# connectors.net
KiCad netlist of a schematic drawn in Altium Designer
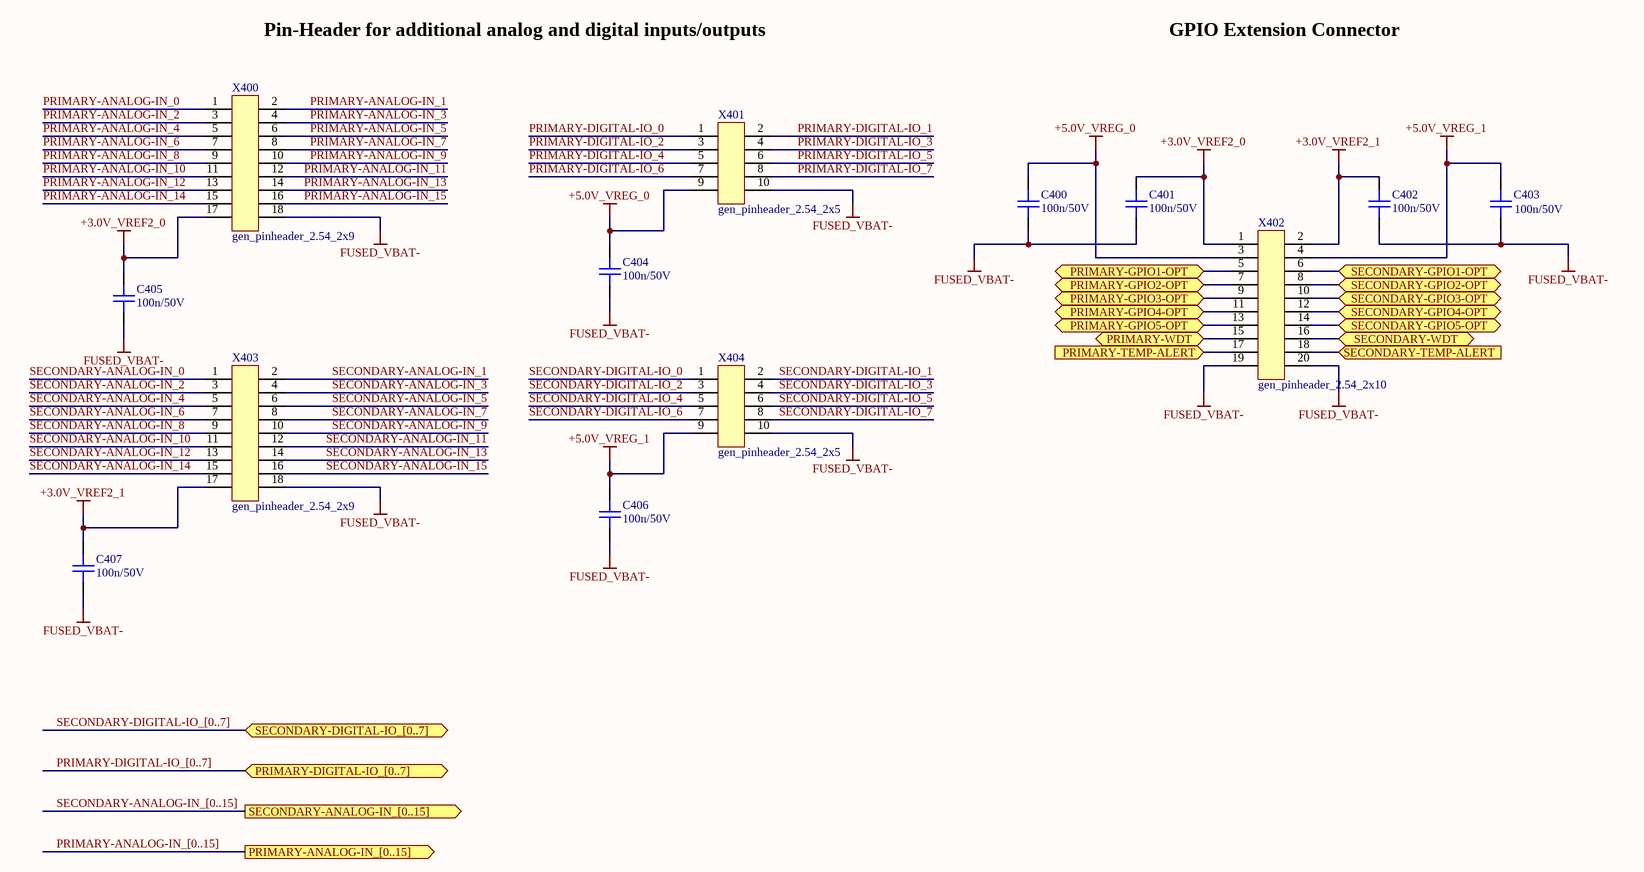
[diagram p0: connectors.SchDoc]

(export (version "E")
  (design (tool "Eeschema 10.0.6"))
  (components
    (comp (ref "C400")
      (value "100n/50V")
      (footprint "CAPC1608X08N")
      (description "MLCC")
      (fields (field (name "PART NUMBER") "gen_C_ceramic_100n_50V_X7R_0603"))
      (libsource (lib "OE750") (part "C"))
    )
    (comp (ref "C401")
      (value "100n/50V")
      (footprint "CAPC1608X08N")
      (description "MLCC")
      (fields (field (name "PART NUMBER") "gen_C_ceramic_100n_50V_X7R_0603"))
      (libsource (lib "OE750") (part "C"))
    )
    (comp (ref "C402")
      (value "100n/50V")
      (footprint "CAPC1608X08N")
      (description "MLCC")
      (fields (field (name "PART NUMBER") "gen_C_ceramic_100n_50V_X7R_0603"))
      (libsource (lib "OE750") (part "C"))
    )
    (comp (ref "C403")
      (value "100n/50V")
      (footprint "CAPC1608X08N")
      (description "MLCC")
      (fields (field (name "PART NUMBER") "gen_C_ceramic_100n_50V_X7R_0603"))
      (libsource (lib "OE750") (part "C"))
    )
    (comp (ref "C404")
      (value "100n/50V")
      (footprint "CAPC1608X08N")
      (description "MLCC")
      (fields (field (name "PART NUMBER") "gen_C_ceramic_100n_50V_X7R_0603"))
      (libsource (lib "OE750") (part "C"))
    )
    (comp (ref "C405")
      (value "100n/50V")
      (footprint "CAPC1608X08N")
      (description "MLCC")
      (fields (field (name "PART NUMBER") "gen_C_ceramic_100n_50V_X7R_0603"))
      (libsource (lib "OE750") (part "C"))
    )
    (comp (ref "C406")
      (value "100n/50V")
      (footprint "CAPC1608X08N")
      (description "MLCC")
      (fields (field (name "PART NUMBER") "gen_C_ceramic_100n_50V_X7R_0603"))
      (libsource (lib "OE750") (part "C"))
    )
    (comp (ref "C407")
      (value "100n/50V")
      (footprint "CAPC1608X08N")
      (description "MLCC")
      (fields (field (name "PART NUMBER") "gen_C_ceramic_100n_50V_X7R_0603"))
      (libsource (lib "OE750") (part "C"))
    )
    (comp (ref "X400")
      (value "gen_pinheader_2.54_2x9")
      (footprint "Pinheader_2.54_2x9")
      (description "Standard Pinheader, THD, gerade, 2.54mm, 2-reihig")
      (libsource (lib "OE750") (part "X2x9"))
    )
    (comp (ref "X401")
      (value "gen_pinheader_2.54_2x5")
      (footprint "Pinheader_2.54_2x5")
      (description "Standard Pinheader, THD, gerade, 2.54mm, 2-reihig")
      (libsource (lib "OE750") (part "X2x5"))
    )
    (comp (ref "X402")
      (value "gen_pinheader_2.54_2x10")
      (footprint "Pinheader_2.54_2x10")
      (description "Standard Pinheader, THD, gerade, 2.54mm, 2-reihig")
      (libsource (lib "OE750") (part "X2x10"))
    )
    (comp (ref "X403")
      (value "gen_pinheader_2.54_2x9")
      (footprint "Pinheader_2.54_2x9")
      (description "Standard Pinheader, THD, gerade, 2.54mm, 2-reihig")
      (libsource (lib "OE750") (part "X2x9"))
    )
    (comp (ref "X404")
      (value "gen_pinheader_2.54_2x5")
      (footprint "Pinheader_2.54_2x5")
      (description "Standard Pinheader, THD, gerade, 2.54mm, 2-reihig")
      (libsource (lib "OE750") (part "X2x5"))
    )
  )
  (nets
    (net (code "1") (name "+3.0V_VREF2_0") (class "Default")
      (node (ref "C401") (pin "2") (pinfunction "2_2") (pintype "passive"))
      (node (ref "C405") (pin "2") (pinfunction "2_2") (pintype "passive"))
      (node (ref "X400") (pin "17") (pintype "passive"))
      (node (ref "X402") (pin "1") (pintype "passive"))
    )
    (net (code "2") (name "+3.0V_VREF2_1") (class "Default")
      (node (ref "C402") (pin "2") (pinfunction "2_2") (pintype "passive"))
      (node (ref "C407") (pin "2") (pinfunction "2_2") (pintype "passive"))
      (node (ref "X402") (pin "2") (pintype "passive"))
      (node (ref "X403") (pin "17") (pintype "passive"))
    )
    (net (code "3") (name "+5.0V_VREG_0") (class "Default")
      (node (ref "C400") (pin "2") (pinfunction "2_2") (pintype "passive"))
      (node (ref "C404") (pin "2") (pinfunction "2_2") (pintype "passive"))
      (node (ref "X401") (pin "9") (pintype "passive"))
      (node (ref "X402") (pin "3") (pintype "passive"))
    )
    (net (code "4") (name "+5.0V_VREG_1") (class "Default")
      (node (ref "C403") (pin "2") (pinfunction "2_2") (pintype "passive"))
      (node (ref "C406") (pin "2") (pinfunction "2_2") (pintype "passive"))
      (node (ref "X402") (pin "4") (pintype "passive"))
      (node (ref "X404") (pin "9") (pintype "passive"))
    )
    (net (code "5") (name "/PRIMARY-ANALOG-IN_0") (class "Default")
      (node (ref "X400") (pin "1") (pintype "passive"))
    )
    (net (code "6") (name "/PRIMARY-ANALOG-IN_1") (class "Default")
      (node (ref "X400") (pin "2") (pintype "passive"))
    )
    (net (code "7") (name "/PRIMARY-ANALOG-IN_2") (class "Default")
      (node (ref "X400") (pin "3") (pintype "passive"))
    )
    (net (code "8") (name "/PRIMARY-ANALOG-IN_3") (class "Default")
      (node (ref "X400") (pin "4") (pintype "passive"))
    )
    (net (code "9") (name "/PRIMARY-ANALOG-IN_4") (class "Default")
      (node (ref "X400") (pin "5") (pintype "passive"))
    )
    (net (code "10") (name "/PRIMARY-ANALOG-IN_5") (class "Default")
      (node (ref "X400") (pin "6") (pintype "passive"))
    )
    (net (code "11") (name "/PRIMARY-ANALOG-IN_6") (class "Default")
      (node (ref "X400") (pin "7") (pintype "passive"))
    )
    (net (code "12") (name "/PRIMARY-ANALOG-IN_7") (class "Default")
      (node (ref "X400") (pin "8") (pintype "passive"))
    )
    (net (code "13") (name "/PRIMARY-ANALOG-IN_8") (class "Default")
      (node (ref "X400") (pin "9") (pintype "passive"))
    )
    (net (code "14") (name "/PRIMARY-ANALOG-IN_9") (class "Default")
      (node (ref "X400") (pin "10") (pintype "passive"))
    )
    (net (code "15") (name "/PRIMARY-ANALOG-IN_10") (class "Default")
      (node (ref "X400") (pin "11") (pintype "passive"))
    )
    (net (code "16") (name "/PRIMARY-ANALOG-IN_11") (class "Default")
      (node (ref "X400") (pin "12") (pintype "passive"))
    )
    (net (code "17") (name "/PRIMARY-ANALOG-IN_12") (class "Default")
      (node (ref "X400") (pin "13") (pintype "passive"))
    )
    (net (code "18") (name "/PRIMARY-ANALOG-IN_13") (class "Default")
      (node (ref "X400") (pin "14") (pintype "passive"))
    )
    (net (code "19") (name "/PRIMARY-ANALOG-IN_14") (class "Default")
      (node (ref "X400") (pin "15") (pintype "passive"))
    )
    (net (code "20") (name "/PRIMARY-ANALOG-IN_15") (class "Default")
      (node (ref "X400") (pin "16") (pintype "passive"))
    )
    (net (code "22") (name "/PRIMARY-DIGITAL-IO_0") (class "Default")
      (node (ref "X401") (pin "1") (pintype "passive"))
    )
    (net (code "23") (name "/PRIMARY-DIGITAL-IO_1") (class "Default")
      (node (ref "X401") (pin "2") (pintype "passive"))
    )
    (net (code "24") (name "/PRIMARY-DIGITAL-IO_2") (class "Default")
      (node (ref "X401") (pin "3") (pintype "passive"))
    )
    (net (code "25") (name "/PRIMARY-DIGITAL-IO_3") (class "Default")
      (node (ref "X401") (pin "4") (pintype "passive"))
    )
    (net (code "26") (name "/PRIMARY-DIGITAL-IO_4") (class "Default")
      (node (ref "X401") (pin "5") (pintype "passive"))
    )
    (net (code "27") (name "/PRIMARY-DIGITAL-IO_5") (class "Default")
      (node (ref "X401") (pin "6") (pintype "passive"))
    )
    (net (code "28") (name "/PRIMARY-DIGITAL-IO_6") (class "Default")
      (node (ref "X401") (pin "7") (pintype "passive"))
    )
    (net (code "29") (name "/PRIMARY-DIGITAL-IO_7") (class "Default")
      (node (ref "X401") (pin "8") (pintype "passive"))
    )
    (net (code "31") (name "/PRIMARY-GPIO1-OPT") (class "Default")
      (node (ref "X402") (pin "5") (pintype "passive"))
    )
    (net (code "32") (name "/PRIMARY-GPIO2-OPT") (class "Default")
      (node (ref "X402") (pin "7") (pintype "passive"))
    )
    (net (code "33") (name "/PRIMARY-GPIO3-OPT") (class "Default")
      (node (ref "X402") (pin "9") (pintype "passive"))
    )
    (net (code "34") (name "/PRIMARY-GPIO4-OPT") (class "Default")
      (node (ref "X402") (pin "11") (pintype "passive"))
    )
    (net (code "35") (name "/PRIMARY-GPIO5-OPT") (class "Default")
      (node (ref "X402") (pin "13") (pintype "passive"))
    )
    (net (code "36") (name "/PRIMARY-TEMP-ALERT") (class "Default")
      (node (ref "X402") (pin "17") (pintype "passive"))
    )
    (net (code "37") (name "/PRIMARY-WDT") (class "Default")
      (node (ref "X402") (pin "15") (pintype "passive"))
    )
    (net (code "38") (name "/SECONDARY-ANALOG-IN_0") (class "Default")
      (node (ref "X403") (pin "1") (pintype "passive"))
    )
    (net (code "39") (name "/SECONDARY-ANALOG-IN_1") (class "Default")
      (node (ref "X403") (pin "2") (pintype "passive"))
    )
    (net (code "40") (name "/SECONDARY-ANALOG-IN_2") (class "Default")
      (node (ref "X403") (pin "3") (pintype "passive"))
    )
    (net (code "41") (name "/SECONDARY-ANALOG-IN_3") (class "Default")
      (node (ref "X403") (pin "4") (pintype "passive"))
    )
    (net (code "42") (name "/SECONDARY-ANALOG-IN_4") (class "Default")
      (node (ref "X403") (pin "5") (pintype "passive"))
    )
    (net (code "43") (name "/SECONDARY-ANALOG-IN_5") (class "Default")
      (node (ref "X403") (pin "6") (pintype "passive"))
    )
    (net (code "44") (name "/SECONDARY-ANALOG-IN_6") (class "Default")
      (node (ref "X403") (pin "7") (pintype "passive"))
    )
    (net (code "45") (name "/SECONDARY-ANALOG-IN_7") (class "Default")
      (node (ref "X403") (pin "8") (pintype "passive"))
    )
    (net (code "46") (name "/SECONDARY-ANALOG-IN_8") (class "Default")
      (node (ref "X403") (pin "9") (pintype "passive"))
    )
    (net (code "47") (name "/SECONDARY-ANALOG-IN_9") (class "Default")
      (node (ref "X403") (pin "10") (pintype "passive"))
    )
    (net (code "48") (name "/SECONDARY-ANALOG-IN_10") (class "Default")
      (node (ref "X403") (pin "11") (pintype "passive"))
    )
    (net (code "49") (name "/SECONDARY-ANALOG-IN_11") (class "Default")
      (node (ref "X403") (pin "12") (pintype "passive"))
    )
    (net (code "50") (name "/SECONDARY-ANALOG-IN_12") (class "Default")
      (node (ref "X403") (pin "13") (pintype "passive"))
    )
    (net (code "51") (name "/SECONDARY-ANALOG-IN_13") (class "Default")
      (node (ref "X403") (pin "14") (pintype "passive"))
    )
    (net (code "52") (name "/SECONDARY-ANALOG-IN_14") (class "Default")
      (node (ref "X403") (pin "15") (pintype "passive"))
    )
    (net (code "53") (name "/SECONDARY-ANALOG-IN_15") (class "Default")
      (node (ref "X403") (pin "16") (pintype "passive"))
    )
    (net (code "55") (name "/SECONDARY-DIGITAL-IO_0") (class "Default")
      (node (ref "X404") (pin "1") (pintype "passive"))
    )
    (net (code "56") (name "/SECONDARY-DIGITAL-IO_1") (class "Default")
      (node (ref "X404") (pin "2") (pintype "passive"))
    )
    (net (code "57") (name "/SECONDARY-DIGITAL-IO_2") (class "Default")
      (node (ref "X404") (pin "3") (pintype "passive"))
    )
    (net (code "58") (name "/SECONDARY-DIGITAL-IO_3") (class "Default")
      (node (ref "X404") (pin "4") (pintype "passive"))
    )
    (net (code "59") (name "/SECONDARY-DIGITAL-IO_4") (class "Default")
      (node (ref "X404") (pin "5") (pintype "passive"))
    )
    (net (code "60") (name "/SECONDARY-DIGITAL-IO_5") (class "Default")
      (node (ref "X404") (pin "6") (pintype "passive"))
    )
    (net (code "61") (name "/SECONDARY-DIGITAL-IO_6") (class "Default")
      (node (ref "X404") (pin "7") (pintype "passive"))
    )
    (net (code "62") (name "/SECONDARY-DIGITAL-IO_7") (class "Default")
      (node (ref "X404") (pin "8") (pintype "passive"))
    )
    (net (code "64") (name "/SECONDARY-GPIO1-OPT") (class "Default")
      (node (ref "X402") (pin "6") (pintype "passive"))
    )
    (net (code "65") (name "/SECONDARY-GPIO2-OPT") (class "Default")
      (node (ref "X402") (pin "8") (pintype "passive"))
    )
    (net (code "66") (name "/SECONDARY-GPIO3-OPT") (class "Default")
      (node (ref "X402") (pin "10") (pintype "passive"))
    )
    (net (code "67") (name "/SECONDARY-GPIO4-OPT") (class "Default")
      (node (ref "X402") (pin "12") (pintype "passive"))
    )
    (net (code "68") (name "/SECONDARY-GPIO5-OPT") (class "Default")
      (node (ref "X402") (pin "14") (pintype "passive"))
    )
    (net (code "69") (name "/SECONDARY-TEMP-ALERT") (class "Default")
      (node (ref "X402") (pin "18") (pintype "passive"))
    )
    (net (code "70") (name "/SECONDARY-WDT") (class "Default")
      (node (ref "X402") (pin "16") (pintype "passive"))
    )
    (net (code "71") (name "FUSED_VBAT-") (class "Default")
      (node (ref "C400") (pin "1") (pinfunction "1_1") (pintype "passive"))
      (node (ref "C401") (pin "1") (pinfunction "1_1") (pintype "passive"))
      (node (ref "C402") (pin "1") (pinfunction "1_1") (pintype "passive"))
      (node (ref "C403") (pin "1") (pinfunction "1_1") (pintype "passive"))
      (node (ref "C404") (pin "1") (pinfunction "1_1") (pintype "passive"))
      (node (ref "C405") (pin "1") (pinfunction "1_1") (pintype "passive"))
      (node (ref "C406") (pin "1") (pinfunction "1_1") (pintype "passive"))
      (node (ref "C407") (pin "1") (pinfunction "1_1") (pintype "passive"))
      (node (ref "X400") (pin "18") (pintype "passive"))
      (node (ref "X401") (pin "10") (pintype "passive"))
      (node (ref "X402") (pin "19") (pintype "passive"))
      (node (ref "X402") (pin "20") (pintype "passive"))
      (node (ref "X403") (pin "18") (pintype "passive"))
      (node (ref "X404") (pin "10") (pintype "passive"))
    )
  )
)
